# uv-exposure-box-main.net
KiCad netlist of a schematic drawn in EAGLE
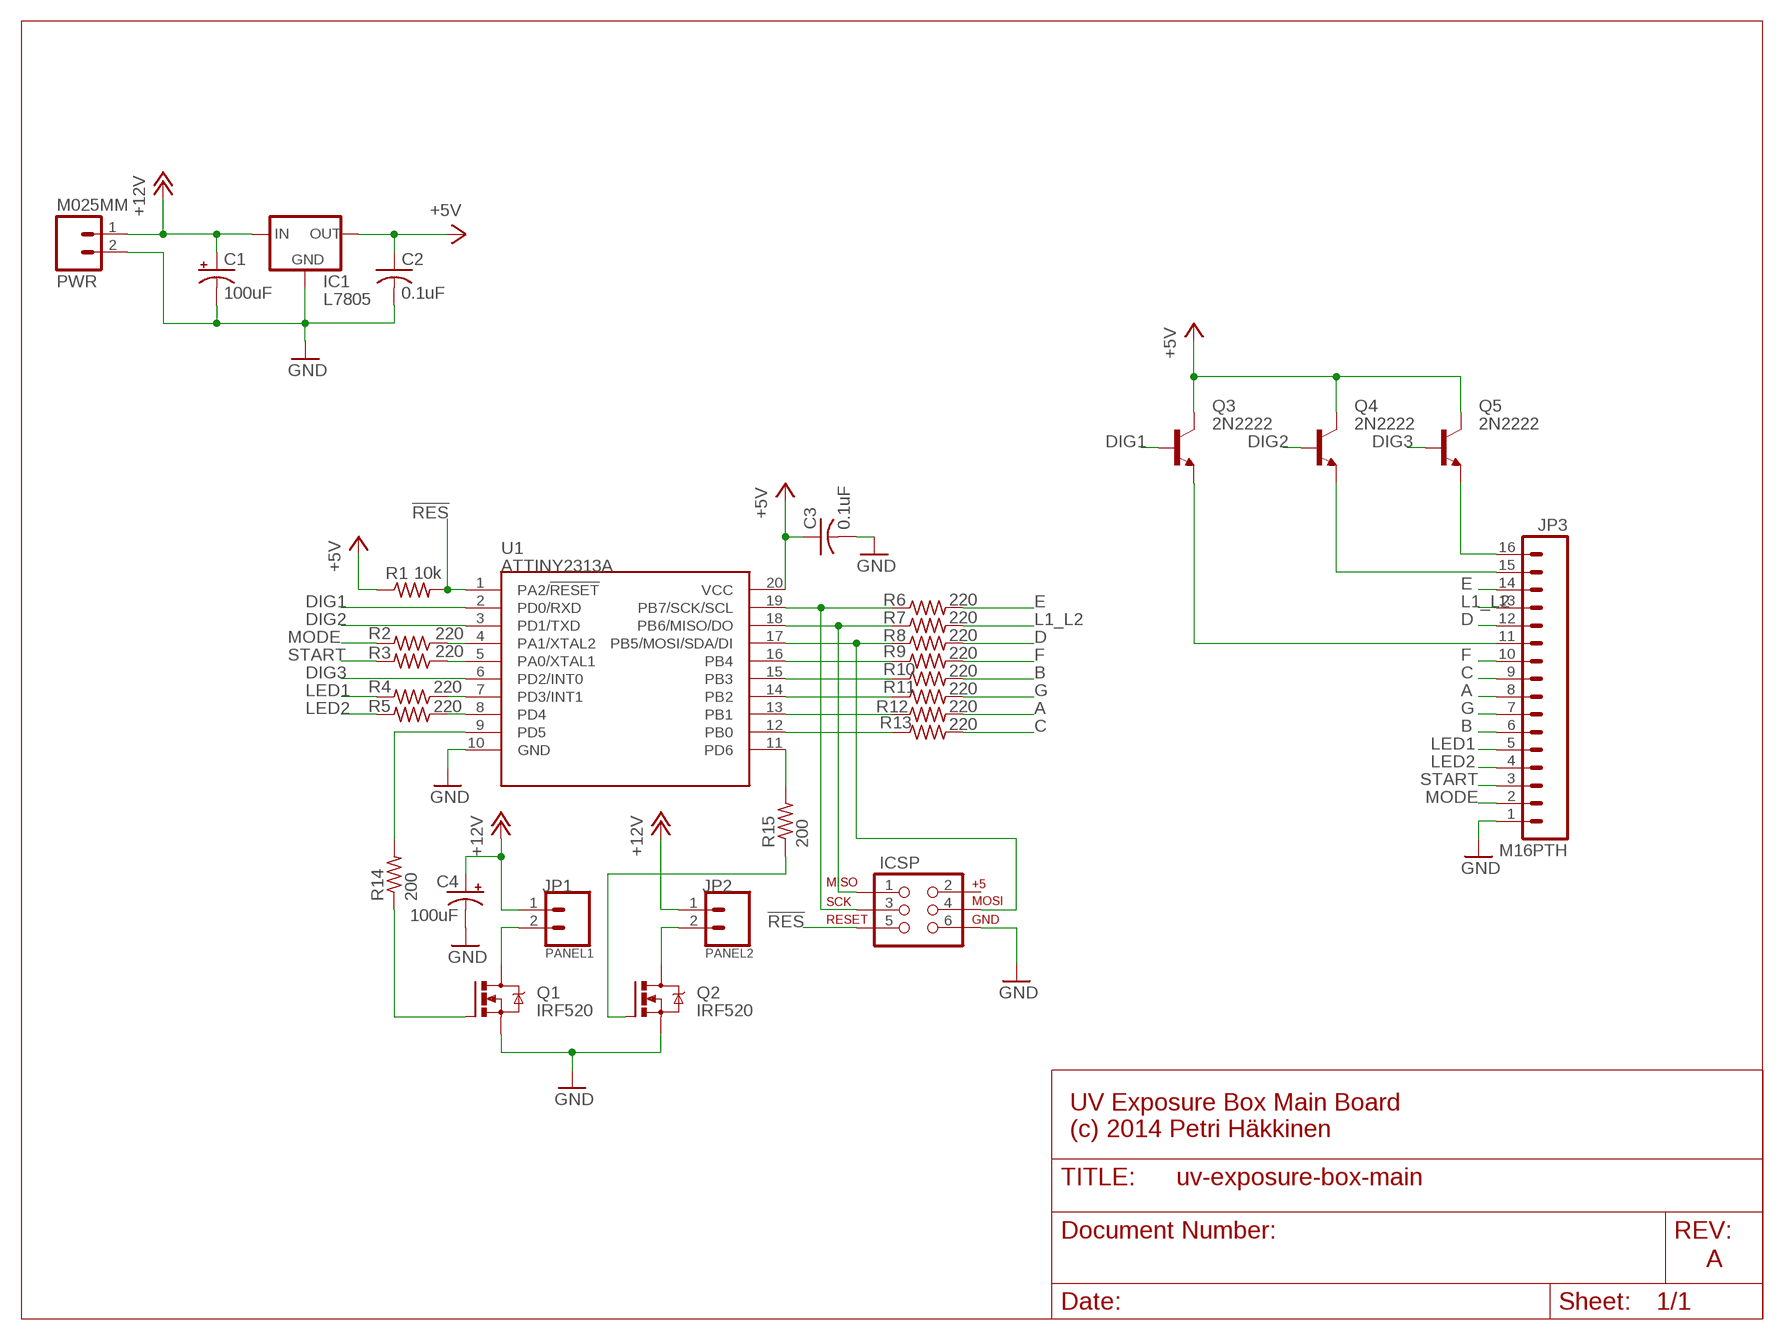
[diagram p0: schematic, sheet 1]

(export (version "E")
  (design (tool "Eeschema 10.0.6"))
  (components
    (comp (ref "C1")
      (value "100uF")
      (footprint "eagle-import:E2,5-5")
      (libsource (lib "eagle-import") (part "CPOL-USE2.5-5"))
    )
    (comp (ref "C2")
      (value "0.1uF")
      (footprint "eagle-import:C025-024X044")
      (libsource (lib "eagle-import") (part "C-US025-024X044"))
    )
    (comp (ref "C3")
      (value "0.1uF")
      (footprint "eagle-import:C025-024X044")
      (libsource (lib "eagle-import") (part "C-US025-024X044"))
    )
    (comp (ref "C4")
      (value "100uF")
      (footprint "eagle-import:E2,5-5")
      (libsource (lib "eagle-import") (part "CPOL-USE2.5-5"))
    )
    (comp (ref "IC1")
      (value "L7805")
      (footprint "eagle-import:TO220-IGO")
      (libsource (lib "eagle-import") (part "V_REG_78XXV"))
    )
    (comp (ref "ICSP")
      (value "AVR_SPI_PRG_6PTH")
      (footprint "eagle-import:2X3")
      (libsource (lib "eagle-import") (part "AVR_SPI_PRG_6PTH"))
    )
    (comp (ref "JP1")
      (value "M025MM")
      (footprint "eagle-import:SCREWTERMINAL-5MM-2")
      (libsource (lib "eagle-import") (part "M025MM"))
    )
    (comp (ref "JP2")
      (value "M025MM")
      (footprint "eagle-import:SCREWTERMINAL-5MM-2")
      (libsource (lib "eagle-import") (part "M025MM"))
    )
    (comp (ref "JP3")
      (value "M16PTH")
      (footprint "eagle-import:1X16")
      (libsource (lib "eagle-import") (part "M16PTH"))
    )
    (comp (ref "PWR")
      (value "M025MM")
      (footprint "eagle-import:SCREWTERMINAL-5MM-2")
      (libsource (lib "eagle-import") (part "M025MM"))
    )
    (comp (ref "Q1")
      (value "IRF520")
      (footprint "eagle-import:TO220BV")
      (libsource (lib "eagle-import") (part "IRF520"))
    )
    (comp (ref "Q2")
      (value "IRF520")
      (footprint "eagle-import:TO220BV")
      (libsource (lib "eagle-import") (part "IRF520"))
    )
    (comp (ref "Q3")
      (value "2N2222")
      (footprint "eagle-import:TO92-EBC")
      (libsource (lib "eagle-import") (part "-NPN-TO92-EBC2N2222"))
    )
    (comp (ref "Q4")
      (value "2N2222")
      (footprint "eagle-import:TO92-EBC")
      (libsource (lib "eagle-import") (part "-NPN-TO92-EBC2N2222"))
    )
    (comp (ref "Q5")
      (value "2N2222")
      (footprint "eagle-import:TO92-EBC")
      (libsource (lib "eagle-import") (part "-NPN-TO92-EBC2N2222"))
    )
    (comp (ref "R1")
      (value "10k")
      (footprint "eagle-import:0207_10")
      (libsource (lib "eagle-import") (part "R-US_0207/10"))
    )
    (comp (ref "R2")
      (value "220")
      (footprint "eagle-import:0207_10")
      (libsource (lib "eagle-import") (part "R-US_0207/10"))
    )
    (comp (ref "R3")
      (value "220")
      (footprint "eagle-import:0207_10")
      (libsource (lib "eagle-import") (part "R-US_0207/10"))
    )
    (comp (ref "R4")
      (value "220")
      (footprint "eagle-import:0207_10")
      (libsource (lib "eagle-import") (part "R-US_0207/10"))
    )
    (comp (ref "R5")
      (value "220")
      (footprint "eagle-import:0207_10")
      (libsource (lib "eagle-import") (part "R-US_0207/10"))
    )
    (comp (ref "R6")
      (value "220")
      (footprint "eagle-import:0207_10")
      (libsource (lib "eagle-import") (part "R-US_0207/10"))
    )
    (comp (ref "R7")
      (value "220")
      (footprint "eagle-import:0207_10")
      (libsource (lib "eagle-import") (part "R-US_0207/10"))
    )
    (comp (ref "R8")
      (value "220")
      (footprint "eagle-import:0207_10")
      (libsource (lib "eagle-import") (part "R-US_0207/10"))
    )
    (comp (ref "R9")
      (value "220")
      (footprint "eagle-import:0207_10")
      (libsource (lib "eagle-import") (part "R-US_0207/10"))
    )
    (comp (ref "R10")
      (value "220")
      (footprint "eagle-import:0207_10")
      (libsource (lib "eagle-import") (part "R-US_0207/10"))
    )
    (comp (ref "R11")
      (value "220")
      (footprint "eagle-import:0207_10")
      (libsource (lib "eagle-import") (part "R-US_0207/10"))
    )
    (comp (ref "R12")
      (value "220")
      (footprint "eagle-import:0207_10")
      (libsource (lib "eagle-import") (part "R-US_0207/10"))
    )
    (comp (ref "R13")
      (value "220")
      (footprint "eagle-import:0207_10")
      (libsource (lib "eagle-import") (part "R-US_0207/10"))
    )
    (comp (ref "R14")
      (value "200")
      (footprint "eagle-import:0207_10")
      (libsource (lib "eagle-import") (part "R-US_0207/10"))
    )
    (comp (ref "R15")
      (value "200")
      (footprint "eagle-import:0207_10")
      (libsource (lib "eagle-import") (part "R-US_0207/10"))
    )
    (comp (ref "U1")
      (value "ATTINY2313A")
      (footprint "eagle-import:DIL20")
      (libsource (lib "eagle-import") (part "ATTINY2313ADIL20"))
    )
  )
  (nets
    (net (code "1") (name "+5V") (class "Default")
      (node (ref "C2") (pin "1") (pinfunction "1_1") (pintype "passive"))
      (node (ref "C3") (pin "1") (pinfunction "1_1") (pintype "passive"))
      (node (ref "IC1") (pin "OUT") (pinfunction "OUT_OUT") (pintype "output"))
      (node (ref "Q3") (pin "C") (pinfunction "C_C") (pintype "passive"))
      (node (ref "Q4") (pin "C") (pinfunction "C_C") (pintype "passive"))
      (node (ref "Q5") (pin "C") (pinfunction "C_C") (pintype "passive"))
      (node (ref "R1") (pin "1") (pinfunction "1_1") (pintype "passive"))
      (node (ref "U1") (pin "20") (pinfunction "VCC_20") (pintype "bidirectional"))
    )
    (net (code "2") (name "+12V") (class "Default")
      (node (ref "C1") (pin "+") (pinfunction "+_+") (pintype "passive"))
      (node (ref "C4") (pin "+") (pinfunction "+_+") (pintype "passive"))
      (node (ref "IC1") (pin "IN") (pinfunction "IN_IN") (pintype "input"))
      (node (ref "JP1") (pin "1") (pinfunction "1_1") (pintype "passive"))
      (node (ref "JP2") (pin "1") (pinfunction "1_1") (pintype "passive"))
      (node (ref "PWR") (pin "1") (pinfunction "1_1") (pintype "passive"))
    )
    (net (code "3") (name "/A") (class "Default")
      (node (ref "JP3") (pin "8") (pinfunction "8_8") (pintype "passive"))
      (node (ref "R12") (pin "2") (pinfunction "2_2") (pintype "passive"))
    )
    (net (code "4") (name "/B") (class "Default")
      (node (ref "JP3") (pin "6") (pinfunction "6_6") (pintype "passive"))
      (node (ref "R10") (pin "2") (pinfunction "2_2") (pintype "passive"))
    )
    (net (code "5") (name "/C") (class "Default")
      (node (ref "JP3") (pin "9") (pinfunction "9_9") (pintype "passive"))
      (node (ref "R13") (pin "2") (pinfunction "2_2") (pintype "passive"))
    )
    (net (code "6") (name "/D") (class "Default")
      (node (ref "JP3") (pin "12") (pinfunction "12_12") (pintype "passive"))
      (node (ref "R8") (pin "2") (pinfunction "2_2") (pintype "passive"))
    )
    (net (code "7") (name "/DIG1") (class "Default")
      (node (ref "Q3") (pin "B") (pinfunction "B_B") (pintype "passive"))
      (node (ref "U1") (pin "2") (pinfunction "PD0/RXD_2") (pintype "bidirectional"))
    )
    (net (code "8") (name "/DIG2") (class "Default")
      (node (ref "Q4") (pin "B") (pinfunction "B_B") (pintype "passive"))
      (node (ref "U1") (pin "3") (pinfunction "PD1/TXD_3") (pintype "bidirectional"))
    )
    (net (code "9") (name "/DIG3") (class "Default")
      (node (ref "Q5") (pin "B") (pinfunction "B_B") (pintype "passive"))
      (node (ref "U1") (pin "6") (pinfunction "PD2/INT0_6") (pintype "bidirectional"))
    )
    (net (code "10") (name "/E") (class "Default")
      (node (ref "JP3") (pin "14") (pinfunction "14_14") (pintype "passive"))
      (node (ref "R6") (pin "2") (pinfunction "2_2") (pintype "passive"))
    )
    (net (code "11") (name "/F") (class "Default")
      (node (ref "JP3") (pin "10") (pinfunction "10_10") (pintype "passive"))
      (node (ref "R9") (pin "2") (pinfunction "2_2") (pintype "passive"))
    )
    (net (code "12") (name "/G") (class "Default")
      (node (ref "JP3") (pin "7") (pinfunction "7_7") (pintype "passive"))
      (node (ref "R11") (pin "2") (pinfunction "2_2") (pintype "passive"))
    )
    (net (code "13") (name "/L1_L2") (class "Default")
      (node (ref "JP3") (pin "13") (pinfunction "13_13") (pintype "passive"))
      (node (ref "R7") (pin "2") (pinfunction "2_2") (pintype "passive"))
    )
    (net (code "14") (name "/LED1") (class "Default")
      (node (ref "JP3") (pin "5") (pinfunction "5_5") (pintype "passive"))
      (node (ref "R4") (pin "2") (pinfunction "2_2") (pintype "passive"))
    )
    (net (code "15") (name "/LED2") (class "Default")
      (node (ref "JP3") (pin "4") (pinfunction "4_4") (pintype "passive"))
      (node (ref "R5") (pin "2") (pinfunction "2_2") (pintype "passive"))
    )
    (net (code "16") (name "/MODE") (class "Default")
      (node (ref "JP3") (pin "2") (pinfunction "2_2") (pintype "passive"))
      (node (ref "R2") (pin "2") (pinfunction "2_2") (pintype "passive"))
    )
    (net (code "17") (name "/START") (class "Default")
      (node (ref "JP3") (pin "3") (pinfunction "3_3") (pintype "passive"))
      (node (ref "R3") (pin "2") (pinfunction "2_2") (pintype "passive"))
    )
    (net (code "18") (name "/~{RES}") (class "Default")
      (node (ref "ICSP") (pin "5") (pinfunction "5_5") (pintype "passive"))
      (node (ref "R1") (pin "2") (pinfunction "2_2") (pintype "passive"))
      (node (ref "U1") (pin "1") (pinfunction "PA2/~{RESET}_1") (pintype "bidirectional"))
    )
    (net (code "19") (name "GND") (class "Default")
      (node (ref "C1") (pin "-") (pinfunction "-_-") (pintype "passive"))
      (node (ref "C2") (pin "2") (pinfunction "2_2") (pintype "passive"))
      (node (ref "C3") (pin "2") (pinfunction "2_2") (pintype "passive"))
      (node (ref "C4") (pin "-") (pinfunction "-_-") (pintype "passive"))
      (node (ref "IC1") (pin "GND") (pinfunction "GND_GND") (pintype "input"))
      (node (ref "ICSP") (pin "6") (pinfunction "6_6") (pintype "passive"))
      (node (ref "JP3") (pin "1") (pinfunction "1_1") (pintype "passive"))
      (node (ref "PWR") (pin "2") (pinfunction "2_2") (pintype "passive"))
      (node (ref "Q1") (pin "S") (pinfunction "S_S") (pintype "passive"))
      (node (ref "Q2") (pin "S") (pinfunction "S_S") (pintype "passive"))
      (node (ref "U1") (pin "10") (pinfunction "GND_10") (pintype "bidirectional"))
    )
    (net (code "20") (name "Net-(JP1-Pad2)") (class "Default")
      (node (ref "JP1") (pin "2") (pinfunction "2_2") (pintype "passive"))
      (node (ref "Q1") (pin "D") (pinfunction "D_D") (pintype "passive"))
    )
    (net (code "21") (name "Net-(JP2-Pad2)") (class "Default")
      (node (ref "JP2") (pin "2") (pinfunction "2_2") (pintype "passive"))
      (node (ref "Q2") (pin "D") (pinfunction "D_D") (pintype "passive"))
    )
    (net (code "22") (name "Net-(JP3-Pad11)") (class "Default")
      (node (ref "JP3") (pin "11") (pinfunction "11_11") (pintype "passive"))
      (node (ref "Q3") (pin "E") (pinfunction "E_E") (pintype "passive"))
    )
    (net (code "23") (name "Net-(JP3-Pad15)") (class "Default")
      (node (ref "JP3") (pin "15") (pinfunction "15_15") (pintype "passive"))
      (node (ref "Q4") (pin "E") (pinfunction "E_E") (pintype "passive"))
    )
    (net (code "24") (name "Net-(JP3-Pad16)") (class "Default")
      (node (ref "JP3") (pin "16") (pinfunction "16_16") (pintype "passive"))
      (node (ref "Q5") (pin "E") (pinfunction "E_E") (pintype "passive"))
    )
    (net (code "25") (name "Net-(Q1-PadG)") (class "Default")
      (node (ref "Q1") (pin "G") (pinfunction "G_G") (pintype "passive"))
      (node (ref "R14") (pin "1") (pinfunction "1_1") (pintype "passive"))
    )
    (net (code "26") (name "Net-(Q2-PadG)") (class "Default")
      (node (ref "Q2") (pin "G") (pinfunction "G_G") (pintype "passive"))
      (node (ref "R15") (pin "1") (pinfunction "1_1") (pintype "passive"))
    )
    (net (code "27") (name "Net-(U1-PA0{slash}XTAL1)") (class "Default")
      (node (ref "R3") (pin "1") (pinfunction "1_1") (pintype "passive"))
      (node (ref "U1") (pin "5") (pinfunction "PA0/XTAL1_5") (pintype "bidirectional"))
    )
    (net (code "28") (name "Net-(U1-PA1{slash}XTAL2)") (class "Default")
      (node (ref "R2") (pin "1") (pinfunction "1_1") (pintype "passive"))
      (node (ref "U1") (pin "4") (pinfunction "PA1/XTAL2_4") (pintype "bidirectional"))
    )
    (net (code "29") (name "Net-(U1-PB0)") (class "Default")
      (node (ref "R13") (pin "1") (pinfunction "1_1") (pintype "passive"))
      (node (ref "U1") (pin "12") (pinfunction "PB0_12") (pintype "bidirectional"))
    )
    (net (code "30") (name "Net-(U1-PB1)") (class "Default")
      (node (ref "R12") (pin "1") (pinfunction "1_1") (pintype "passive"))
      (node (ref "U1") (pin "13") (pinfunction "PB1_13") (pintype "bidirectional"))
    )
    (net (code "31") (name "Net-(U1-PB2)") (class "Default")
      (node (ref "R11") (pin "1") (pinfunction "1_1") (pintype "passive"))
      (node (ref "U1") (pin "14") (pinfunction "PB2_14") (pintype "bidirectional"))
    )
    (net (code "32") (name "Net-(U1-PB3)") (class "Default")
      (node (ref "R10") (pin "1") (pinfunction "1_1") (pintype "passive"))
      (node (ref "U1") (pin "15") (pinfunction "PB3_15") (pintype "bidirectional"))
    )
    (net (code "33") (name "Net-(U1-PB4)") (class "Default")
      (node (ref "R9") (pin "1") (pinfunction "1_1") (pintype "passive"))
      (node (ref "U1") (pin "16") (pinfunction "PB4_16") (pintype "bidirectional"))
    )
    (net (code "34") (name "Net-(U1-PB5{slash}MOSI{slash}SDA{slash}DI)") (class "Default")
      (node (ref "ICSP") (pin "4") (pinfunction "4_4") (pintype "passive"))
      (node (ref "R8") (pin "1") (pinfunction "1_1") (pintype "passive"))
      (node (ref "U1") (pin "17") (pinfunction "PB5/MOSI/SDA/DI_17") (pintype "bidirectional"))
    )
    (net (code "35") (name "Net-(U1-PB6{slash}MISO{slash}DO)") (class "Default")
      (node (ref "ICSP") (pin "1") (pinfunction "1_1") (pintype "passive"))
      (node (ref "R7") (pin "1") (pinfunction "1_1") (pintype "passive"))
      (node (ref "U1") (pin "18") (pinfunction "PB6/MISO/DO_18") (pintype "bidirectional"))
    )
    (net (code "36") (name "Net-(U1-PB7{slash}SCK{slash}SCL)") (class "Default")
      (node (ref "ICSP") (pin "3") (pinfunction "3_3") (pintype "passive"))
      (node (ref "R6") (pin "1") (pinfunction "1_1") (pintype "passive"))
      (node (ref "U1") (pin "19") (pinfunction "PB7/SCK/SCL_19") (pintype "bidirectional"))
    )
    (net (code "37") (name "Net-(U1-PD3{slash}INT1)") (class "Default")
      (node (ref "R4") (pin "1") (pinfunction "1_1") (pintype "passive"))
      (node (ref "U1") (pin "7") (pinfunction "PD3/INT1_7") (pintype "bidirectional"))
    )
    (net (code "38") (name "Net-(U1-PD4)") (class "Default")
      (node (ref "R5") (pin "1") (pinfunction "1_1") (pintype "passive"))
      (node (ref "U1") (pin "8") (pinfunction "PD4_8") (pintype "bidirectional"))
    )
    (net (code "39") (name "Net-(U1-PD5)") (class "Default")
      (node (ref "R14") (pin "2") (pinfunction "2_2") (pintype "passive"))
      (node (ref "U1") (pin "9") (pinfunction "PD5_9") (pintype "bidirectional"))
    )
    (net (code "40") (name "Net-(U1-PD6)") (class "Default")
      (node (ref "R15") (pin "2") (pinfunction "2_2") (pintype "passive"))
      (node (ref "U1") (pin "11") (pinfunction "PD6_11") (pintype "bidirectional"))
    )
    (net (code "41") (name "unconnected-(ICSP-Pad2)") (class "Default")
      (node (ref "ICSP") (pin "2") (pinfunction "2_2") (pintype "passive"))
    )
  )
)
